# M104D.net
KiCad netlist of a schematic drawn in EAGLE
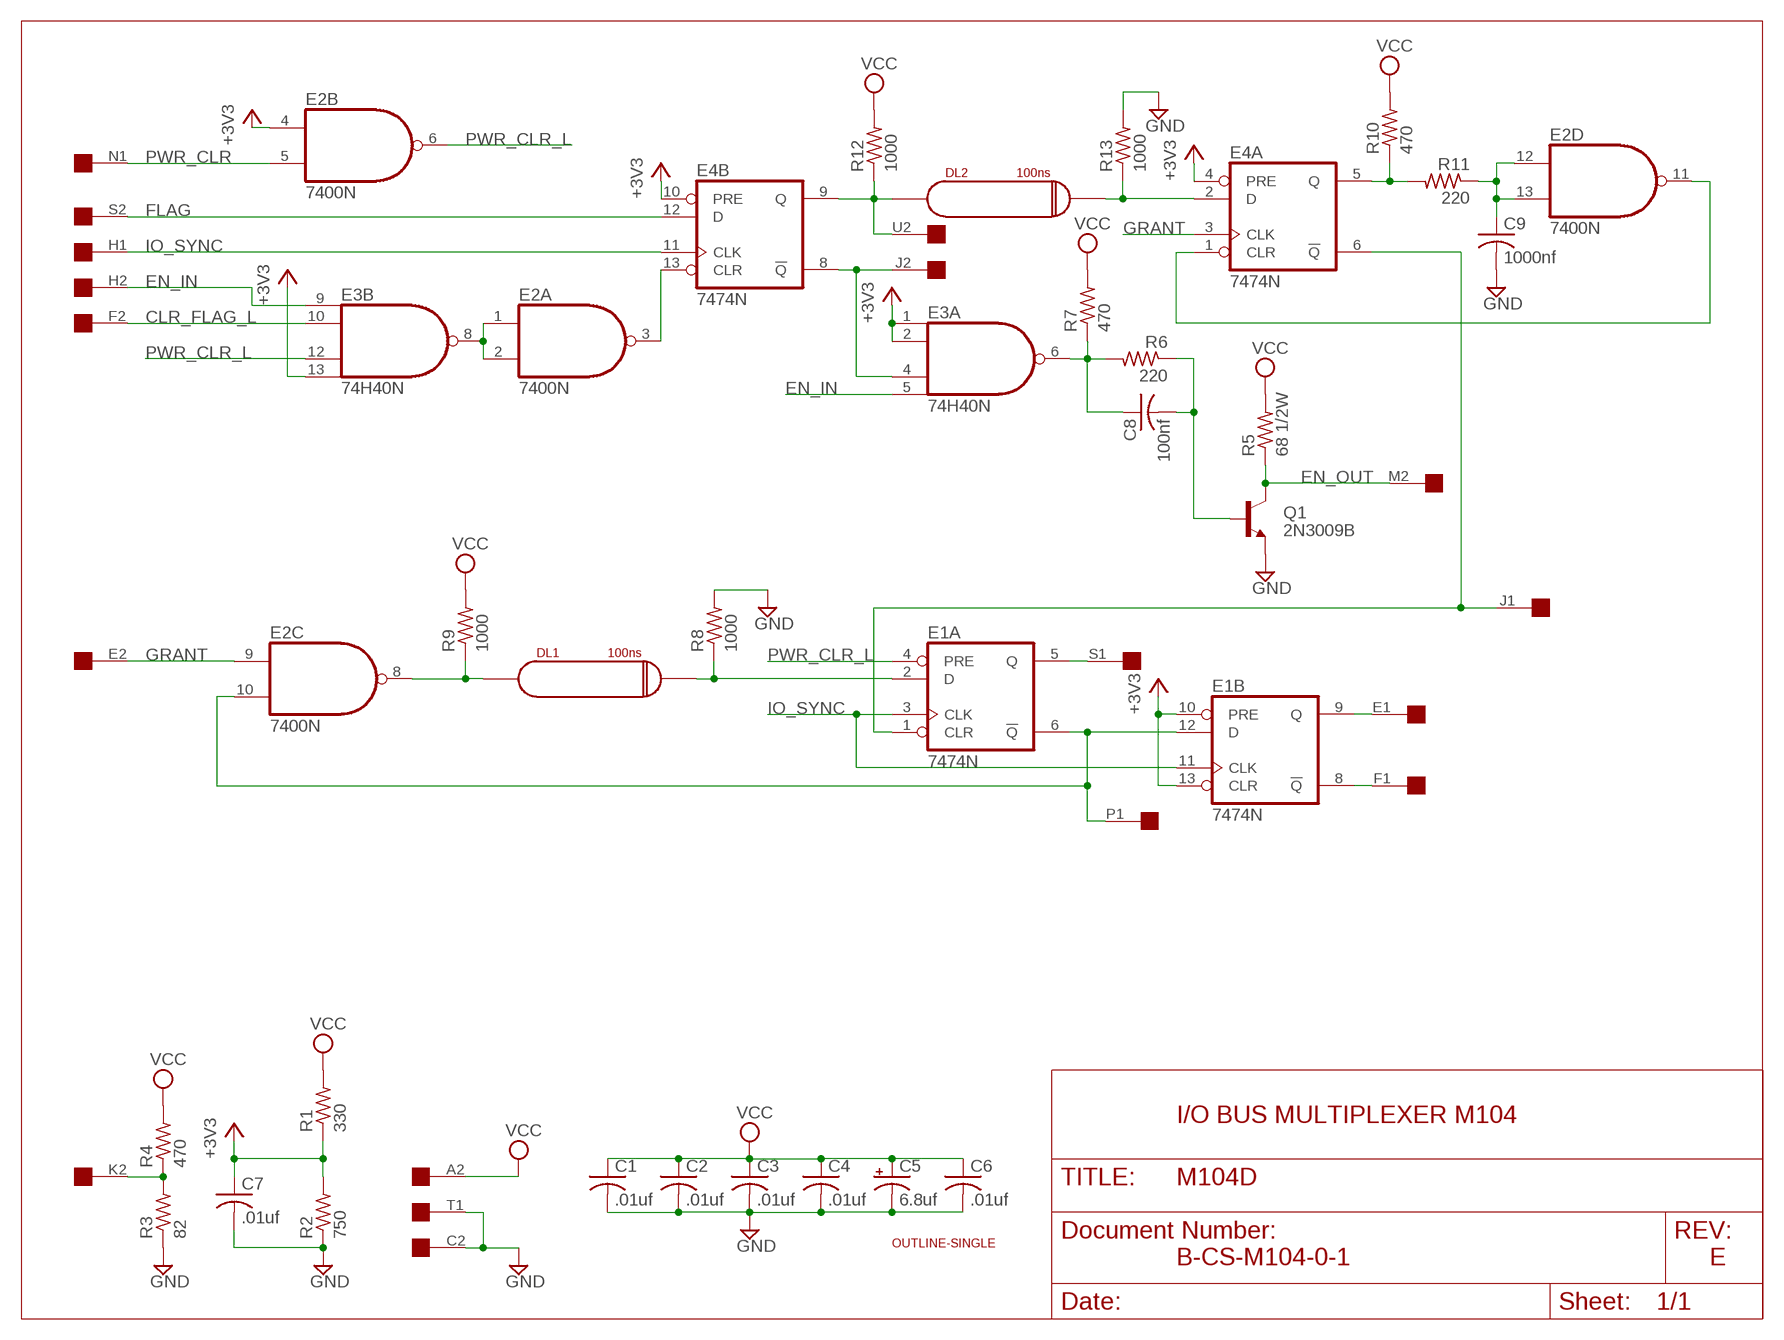
[diagram p0: schematic, sheet 1]

(export (version "E")
  (design (tool "Eeschema 10.0.6"))
  (components
    (comp (ref "C1")
      (value ".01uf")
      (footprint "eagle-import:C050-025X075")
      (libsource (lib "eagle-import") (part "C-US050-025X075"))
    )
    (comp (ref "C2")
      (value ".01uf")
      (footprint "eagle-import:C050-025X075")
      (libsource (lib "eagle-import") (part "C-US050-025X075"))
    )
    (comp (ref "C3")
      (value ".01uf")
      (footprint "eagle-import:C050-025X075")
      (libsource (lib "eagle-import") (part "C-US050-025X075"))
    )
    (comp (ref "C4")
      (value ".01uf")
      (footprint "eagle-import:C050-025X075")
      (libsource (lib "eagle-import") (part "C-US050-025X075"))
    )
    (comp (ref "C5")
      (value "6.8uf")
      (footprint "eagle-import:E15-5")
      (libsource (lib "eagle-import") (part "CPOL-USE15-5AXIAL"))
    )
    (comp (ref "C6")
      (value ".01uf")
      (footprint "eagle-import:C050-025X075")
      (libsource (lib "eagle-import") (part "C-US050-025X075"))
    )
    (comp (ref "C7")
      (value ".01uf")
      (footprint "eagle-import:C050-025X075")
      (libsource (lib "eagle-import") (part "C-US050-025X075"))
    )
    (comp (ref "C8")
      (value "100nf")
      (footprint "eagle-import:C050-025X075")
      (libsource (lib "eagle-import") (part "C-US050-025X075"))
    )
    (comp (ref "C9")
      (value "1000nf")
      (footprint "eagle-import:C050-025X075")
      (libsource (lib "eagle-import") (part "C-US050-025X075"))
    )
    (comp (ref "DL1")
      (value "100ns")
      (footprint "eagle-import:RCL-L-XX-22")
      (libsource (lib "eagle-import") (part "RC-L-22"))
    )
    (comp (ref "DL2")
      (value "100ns")
      (footprint "eagle-import:RCL-L-XX-22")
      (libsource (lib "eagle-import") (part "RC-L-22"))
    )
    (comp (ref "E1")
      (value "7474N")
      (footprint "eagle-import:DIL14")
      (libsource (lib "eagle-import") (part "7474NS"))
    )
    (comp (ref "E2")
      (value "7400N")
      (footprint "eagle-import:DIL14")
      (libsource (lib "eagle-import") (part "7400N"))
    )
    (comp (ref "E3")
      (value "74H40N")
      (footprint "eagle-import:DIL14")
      (libsource (lib "eagle-import") (part "7420NS"))
    )
    (comp (ref "E4")
      (value "7474N")
      (footprint "eagle-import:DIL14")
      (libsource (lib "eagle-import") (part "7474NS"))
    )
    (comp (ref "Q1")
      (value "2N3009B")
      (footprint "eagle-import:TO39")
      (libsource (lib "eagle-import") (part "-NPN-TO39-EBC2N1613"))
    )
    (comp (ref "R1")
      (value "330")
      (footprint "eagle-import:0207_10")
      (libsource (lib "eagle-import") (part "R-US_0207/10"))
    )
    (comp (ref "R2")
      (value "750")
      (footprint "eagle-import:0207_10")
      (libsource (lib "eagle-import") (part "R-US_0207/10"))
    )
    (comp (ref "R3")
      (value "82")
      (footprint "eagle-import:0207_10")
      (libsource (lib "eagle-import") (part "R-US_0207/10"))
    )
    (comp (ref "R4")
      (value "470")
      (footprint "eagle-import:0207_10")
      (libsource (lib "eagle-import") (part "R-US_0207/10"))
    )
    (comp (ref "R5")
      (value "68 1/2W")
      (footprint "eagle-import:0411_15")
      (libsource (lib "eagle-import") (part "R-US_0411/15"))
    )
    (comp (ref "R6")
      (value "220")
      (footprint "eagle-import:0207_10")
      (libsource (lib "eagle-import") (part "R-US_0207/10"))
    )
    (comp (ref "R7")
      (value "470")
      (footprint "eagle-import:0207_10")
      (libsource (lib "eagle-import") (part "R-US_0207/10"))
    )
    (comp (ref "R8")
      (value "1000")
      (footprint "eagle-import:0207_10")
      (libsource (lib "eagle-import") (part "R-US_0207/10"))
    )
    (comp (ref "R9")
      (value "1000")
      (footprint "eagle-import:0207_10")
      (libsource (lib "eagle-import") (part "R-US_0207/10"))
    )
    (comp (ref "R10")
      (value "470")
      (footprint "eagle-import:0207_10")
      (libsource (lib "eagle-import") (part "R-US_0207/10"))
    )
    (comp (ref "R11")
      (value "220")
      (footprint "eagle-import:0207_10")
      (libsource (lib "eagle-import") (part "R-US_0207/10"))
    )
    (comp (ref "R12")
      (value "1000")
      (footprint "eagle-import:0207_10")
      (libsource (lib "eagle-import") (part "R-US_0207/10"))
    )
    (comp (ref "R13")
      (value "1000")
      (footprint "eagle-import:0207_10")
      (libsource (lib "eagle-import") (part "R-US_0207/10"))
    )
    (comp (ref "U$8")
      (value "SINGLE")
      (footprint "eagle-import:EDGE-CON2")
      (libsource (lib "eagle-import") (part "SINGLE"))
    )
    (comp (ref "U$9")
      (value "OUTLINE-SINGLE")
      (footprint "eagle-import:SINGLE")
      (libsource (lib "eagle-import") (part "OUTLINE-SINGLE"))
    )
  )
  (nets
    (net (code "1") (name "+3V3") (class "Default")
      (node (ref "C7") (pin "1") (pinfunction "1_1") (pintype "passive"))
      (node (ref "E1") (pin "10") (pinfunction "PRE_10") (pintype "input"))
      (node (ref "E1") (pin "13") (pinfunction "CLR_13") (pintype "input"))
      (node (ref "E2") (pin "4") (pinfunction "I0_4") (pintype "input"))
      (node (ref "E3") (pin "1") (pinfunction "I0_1") (pintype "input"))
      (node (ref "E3") (pin "13") (pinfunction "I3_13") (pintype "input"))
      (node (ref "E3") (pin "2") (pinfunction "I1_2") (pintype "input"))
      (node (ref "E4") (pin "10") (pinfunction "PRE_10") (pintype "input"))
      (node (ref "E4") (pin "4") (pinfunction "PRE_4") (pintype "input"))
      (node (ref "R1") (pin "1") (pinfunction "1_1") (pintype "passive"))
      (node (ref "R2") (pin "2") (pinfunction "2_2") (pintype "passive"))
    )
    (net (code "2") (name "/CLR_FLAG_L") (class "Default")
      (node (ref "E3") (pin "10") (pinfunction "I1_10") (pintype "input"))
      (node (ref "U$8") (pin "F2") (pinfunction "1_F2") (pintype "bidirectional"))
    )
    (net (code "3") (name "/EN_IN") (class "Default")
      (node (ref "E3") (pin "5") (pinfunction "I3_5") (pintype "input"))
      (node (ref "E3") (pin "9") (pinfunction "I0_9") (pintype "input"))
      (node (ref "U$8") (pin "H2") (pinfunction "1_H2") (pintype "bidirectional"))
    )
    (net (code "4") (name "/EN_OUT") (class "Default")
      (node (ref "Q1") (pin "3") (pinfunction "C_3") (pintype "passive"))
      (node (ref "R5") (pin "1") (pinfunction "1_1") (pintype "passive"))
      (node (ref "U$8") (pin "M2") (pinfunction "1_M2") (pintype "bidirectional"))
    )
    (net (code "5") (name "/FLAG") (class "Default")
      (node (ref "E4") (pin "12") (pinfunction "D_12") (pintype "input"))
      (node (ref "U$8") (pin "S2") (pinfunction "1_S2") (pintype "bidirectional"))
    )
    (net (code "6") (name "/GRANT") (class "Default")
      (node (ref "E2") (pin "9") (pinfunction "I0_9") (pintype "input"))
      (node (ref "E4") (pin "3") (pinfunction "CLK_3") (pintype "input"))
      (node (ref "U$8") (pin "E2") (pinfunction "1_E2") (pintype "bidirectional"))
    )
    (net (code "7") (name "/IO_SYNC") (class "Default")
      (node (ref "E1") (pin "11") (pinfunction "CLK_11") (pintype "input"))
      (node (ref "E1") (pin "3") (pinfunction "CLK_3") (pintype "input"))
      (node (ref "E4") (pin "11") (pinfunction "CLK_11") (pintype "input"))
      (node (ref "U$8") (pin "H1") (pinfunction "1_H1") (pintype "bidirectional"))
    )
    (net (code "8") (name "/PWR_CLR") (class "Default")
      (node (ref "E2") (pin "5") (pinfunction "I1_5") (pintype "input"))
      (node (ref "U$8") (pin "N1") (pinfunction "1_N1") (pintype "bidirectional"))
    )
    (net (code "9") (name "/PWR_CLR_L") (class "Default")
      (node (ref "E1") (pin "4") (pinfunction "PRE_4") (pintype "input"))
      (node (ref "E2") (pin "6") (pinfunction "O_6") (pintype "output"))
      (node (ref "E3") (pin "12") (pinfunction "I2_12") (pintype "input"))
    )
    (net (code "10") (name "GND") (class "Default")
      (node (ref "C1") (pin "2") (pinfunction "2_2") (pintype "passive"))
      (node (ref "C2") (pin "2") (pinfunction "2_2") (pintype "passive"))
      (node (ref "C3") (pin "2") (pinfunction "2_2") (pintype "passive"))
      (node (ref "C4") (pin "2") (pinfunction "2_2") (pintype "passive"))
      (node (ref "C5") (pin "-") (pinfunction "-_-") (pintype "passive"))
      (node (ref "C6") (pin "2") (pinfunction "2_2") (pintype "passive"))
      (node (ref "C7") (pin "2") (pinfunction "2_2") (pintype "passive"))
      (node (ref "C9") (pin "2") (pinfunction "2_2") (pintype "passive"))
      (node (ref "Q1") (pin "1") (pinfunction "E_1") (pintype "passive"))
      (node (ref "R13") (pin "2") (pinfunction "2_2") (pintype "passive"))
      (node (ref "R2") (pin "1") (pinfunction "1_1") (pintype "passive"))
      (node (ref "R3") (pin "1") (pinfunction "1_1") (pintype "passive"))
      (node (ref "R8") (pin "2") (pinfunction "2_2") (pintype "passive"))
      (node (ref "U$8") (pin "C2") (pinfunction "1_C2") (pintype "bidirectional"))
      (node (ref "U$8") (pin "T1") (pinfunction "1_T1") (pintype "bidirectional"))
    )
    (net (code "11") (name "Net-(E1A-CLR)") (class "Default")
      (node (ref "E1") (pin "1") (pinfunction "CLR_1") (pintype "input"))
      (node (ref "E4") (pin "6") (pinfunction "~{Q}_6") (pintype "output"))
      (node (ref "U$8") (pin "J1") (pinfunction "1_J1") (pintype "bidirectional"))
    )
    (net (code "12") (name "Net-(E1A-D)") (class "Default")
      (node (ref "DL1") (pin "OUT") (pinfunction "OUT_OUT") (pintype "bidirectional"))
      (node (ref "E1") (pin "2") (pinfunction "D_2") (pintype "input"))
      (node (ref "R8") (pin "1") (pinfunction "1_1") (pintype "passive"))
    )
    (net (code "13") (name "Net-(E1A-Q)") (class "Default")
      (node (ref "E1") (pin "5") (pinfunction "Q_5") (pintype "output"))
      (node (ref "U$8") (pin "S1") (pinfunction "1_S1") (pintype "bidirectional"))
    )
    (net (code "14") (name "Net-(E1A-~{Q})") (class "Default")
      (node (ref "E1") (pin "12") (pinfunction "D_12") (pintype "input"))
      (node (ref "E1") (pin "6") (pinfunction "~{Q}_6") (pintype "output"))
      (node (ref "E2") (pin "10") (pinfunction "I1_10") (pintype "input"))
      (node (ref "U$8") (pin "P1") (pinfunction "1_P1") (pintype "bidirectional"))
    )
    (net (code "15") (name "Net-(E1B-Q)") (class "Default")
      (node (ref "E1") (pin "9") (pinfunction "Q_9") (pintype "output"))
      (node (ref "U$8") (pin "E1") (pinfunction "1_E1") (pintype "bidirectional"))
    )
    (net (code "16") (name "Net-(E1B-~{Q})") (class "Default")
      (node (ref "E1") (pin "8") (pinfunction "~{Q}_8") (pintype "output"))
      (node (ref "U$8") (pin "F1") (pinfunction "1_F1") (pintype "bidirectional"))
    )
    (net (code "17") (name "Net-(E2A-I0)") (class "Default")
      (node (ref "E2") (pin "1") (pinfunction "I0_1") (pintype "input"))
      (node (ref "E2") (pin "2") (pinfunction "I1_2") (pintype "input"))
      (node (ref "E3") (pin "8") (pinfunction "O_8") (pintype "output"))
    )
    (net (code "18") (name "Net-(E2A-O)") (class "Default")
      (node (ref "E2") (pin "3") (pinfunction "O_3") (pintype "output"))
      (node (ref "E4") (pin "13") (pinfunction "CLR_13") (pintype "input"))
    )
    (net (code "19") (name "Net-(E2C-O)") (class "Default")
      (node (ref "DL1") (pin "IN") (pinfunction "IN_IN") (pintype "bidirectional"))
      (node (ref "E2") (pin "8") (pinfunction "O_8") (pintype "output"))
      (node (ref "R9") (pin "1") (pinfunction "1_1") (pintype "passive"))
    )
    (net (code "20") (name "Net-(E2D-I0)") (class "Default")
      (node (ref "C9") (pin "1") (pinfunction "1_1") (pintype "passive"))
      (node (ref "E2") (pin "12") (pinfunction "I0_12") (pintype "input"))
      (node (ref "E2") (pin "13") (pinfunction "I1_13") (pintype "input"))
      (node (ref "R11") (pin "1") (pinfunction "1_1") (pintype "passive"))
    )
    (net (code "21") (name "Net-(E2D-O)") (class "Default")
      (node (ref "E2") (pin "11") (pinfunction "O_11") (pintype "output"))
      (node (ref "E4") (pin "1") (pinfunction "CLR_1") (pintype "input"))
    )
    (net (code "22") (name "Net-(E3A-I2)") (class "Default")
      (node (ref "E3") (pin "4") (pinfunction "I2_4") (pintype "input"))
      (node (ref "E4") (pin "8") (pinfunction "~{Q}_8") (pintype "output"))
      (node (ref "U$8") (pin "J2") (pinfunction "1_J2") (pintype "bidirectional"))
    )
    (net (code "23") (name "Net-(E3A-O)") (class "Default")
      (node (ref "C8") (pin "1") (pinfunction "1_1") (pintype "passive"))
      (node (ref "E3") (pin "6") (pinfunction "O_6") (pintype "output"))
      (node (ref "R6") (pin "2") (pinfunction "2_2") (pintype "passive"))
      (node (ref "R7") (pin "1") (pinfunction "1_1") (pintype "passive"))
    )
    (net (code "24") (name "Net-(E4A-D)") (class "Default")
      (node (ref "DL2") (pin "OUT") (pinfunction "OUT_OUT") (pintype "bidirectional"))
      (node (ref "E4") (pin "2") (pinfunction "D_2") (pintype "input"))
      (node (ref "R13") (pin "1") (pinfunction "1_1") (pintype "passive"))
    )
    (net (code "25") (name "Net-(E4A-Q)") (class "Default")
      (node (ref "E4") (pin "5") (pinfunction "Q_5") (pintype "output"))
      (node (ref "R10") (pin "1") (pinfunction "1_1") (pintype "passive"))
      (node (ref "R11") (pin "2") (pinfunction "2_2") (pintype "passive"))
    )
    (net (code "26") (name "Net-(E4B-Q)") (class "Default")
      (node (ref "DL2") (pin "IN") (pinfunction "IN_IN") (pintype "bidirectional"))
      (node (ref "E4") (pin "9") (pinfunction "Q_9") (pintype "output"))
      (node (ref "R12") (pin "1") (pinfunction "1_1") (pintype "passive"))
      (node (ref "U$8") (pin "U2") (pinfunction "1_U2") (pintype "bidirectional"))
    )
    (net (code "27") (name "Net-(Q1-B)") (class "Default")
      (node (ref "C8") (pin "2") (pinfunction "2_2") (pintype "passive"))
      (node (ref "Q1") (pin "2") (pinfunction "B_2") (pintype "passive"))
      (node (ref "R6") (pin "1") (pinfunction "1_1") (pintype "passive"))
    )
    (net (code "28") (name "Net-(U$8R-1)") (class "Default")
      (node (ref "R3") (pin "2") (pinfunction "2_2") (pintype "passive"))
      (node (ref "R4") (pin "1") (pinfunction "1_1") (pintype "passive"))
      (node (ref "U$8") (pin "K2") (pinfunction "1_K2") (pintype "bidirectional"))
    )
    (net (code "29") (name "VCC") (class "Default")
      (node (ref "C1") (pin "1") (pinfunction "1_1") (pintype "passive"))
      (node (ref "C2") (pin "1") (pinfunction "1_1") (pintype "passive"))
      (node (ref "C3") (pin "1") (pinfunction "1_1") (pintype "passive"))
      (node (ref "C4") (pin "1") (pinfunction "1_1") (pintype "passive"))
      (node (ref "C5") (pin "+") (pinfunction "+_+") (pintype "passive"))
      (node (ref "C6") (pin "1") (pinfunction "1_1") (pintype "passive"))
      (node (ref "R1") (pin "2") (pinfunction "2_2") (pintype "passive"))
      (node (ref "R10") (pin "2") (pinfunction "2_2") (pintype "passive"))
      (node (ref "R12") (pin "2") (pinfunction "2_2") (pintype "passive"))
      (node (ref "R4") (pin "2") (pinfunction "2_2") (pintype "passive"))
      (node (ref "R5") (pin "2") (pinfunction "2_2") (pintype "passive"))
      (node (ref "R7") (pin "2") (pinfunction "2_2") (pintype "passive"))
      (node (ref "R9") (pin "2") (pinfunction "2_2") (pintype "passive"))
      (node (ref "U$8") (pin "A2") (pinfunction "1_A2") (pintype "bidirectional"))
    )
  )
)
